# openSX70-dongle.net
KiCad netlist of a schematic drawn in EAGLE
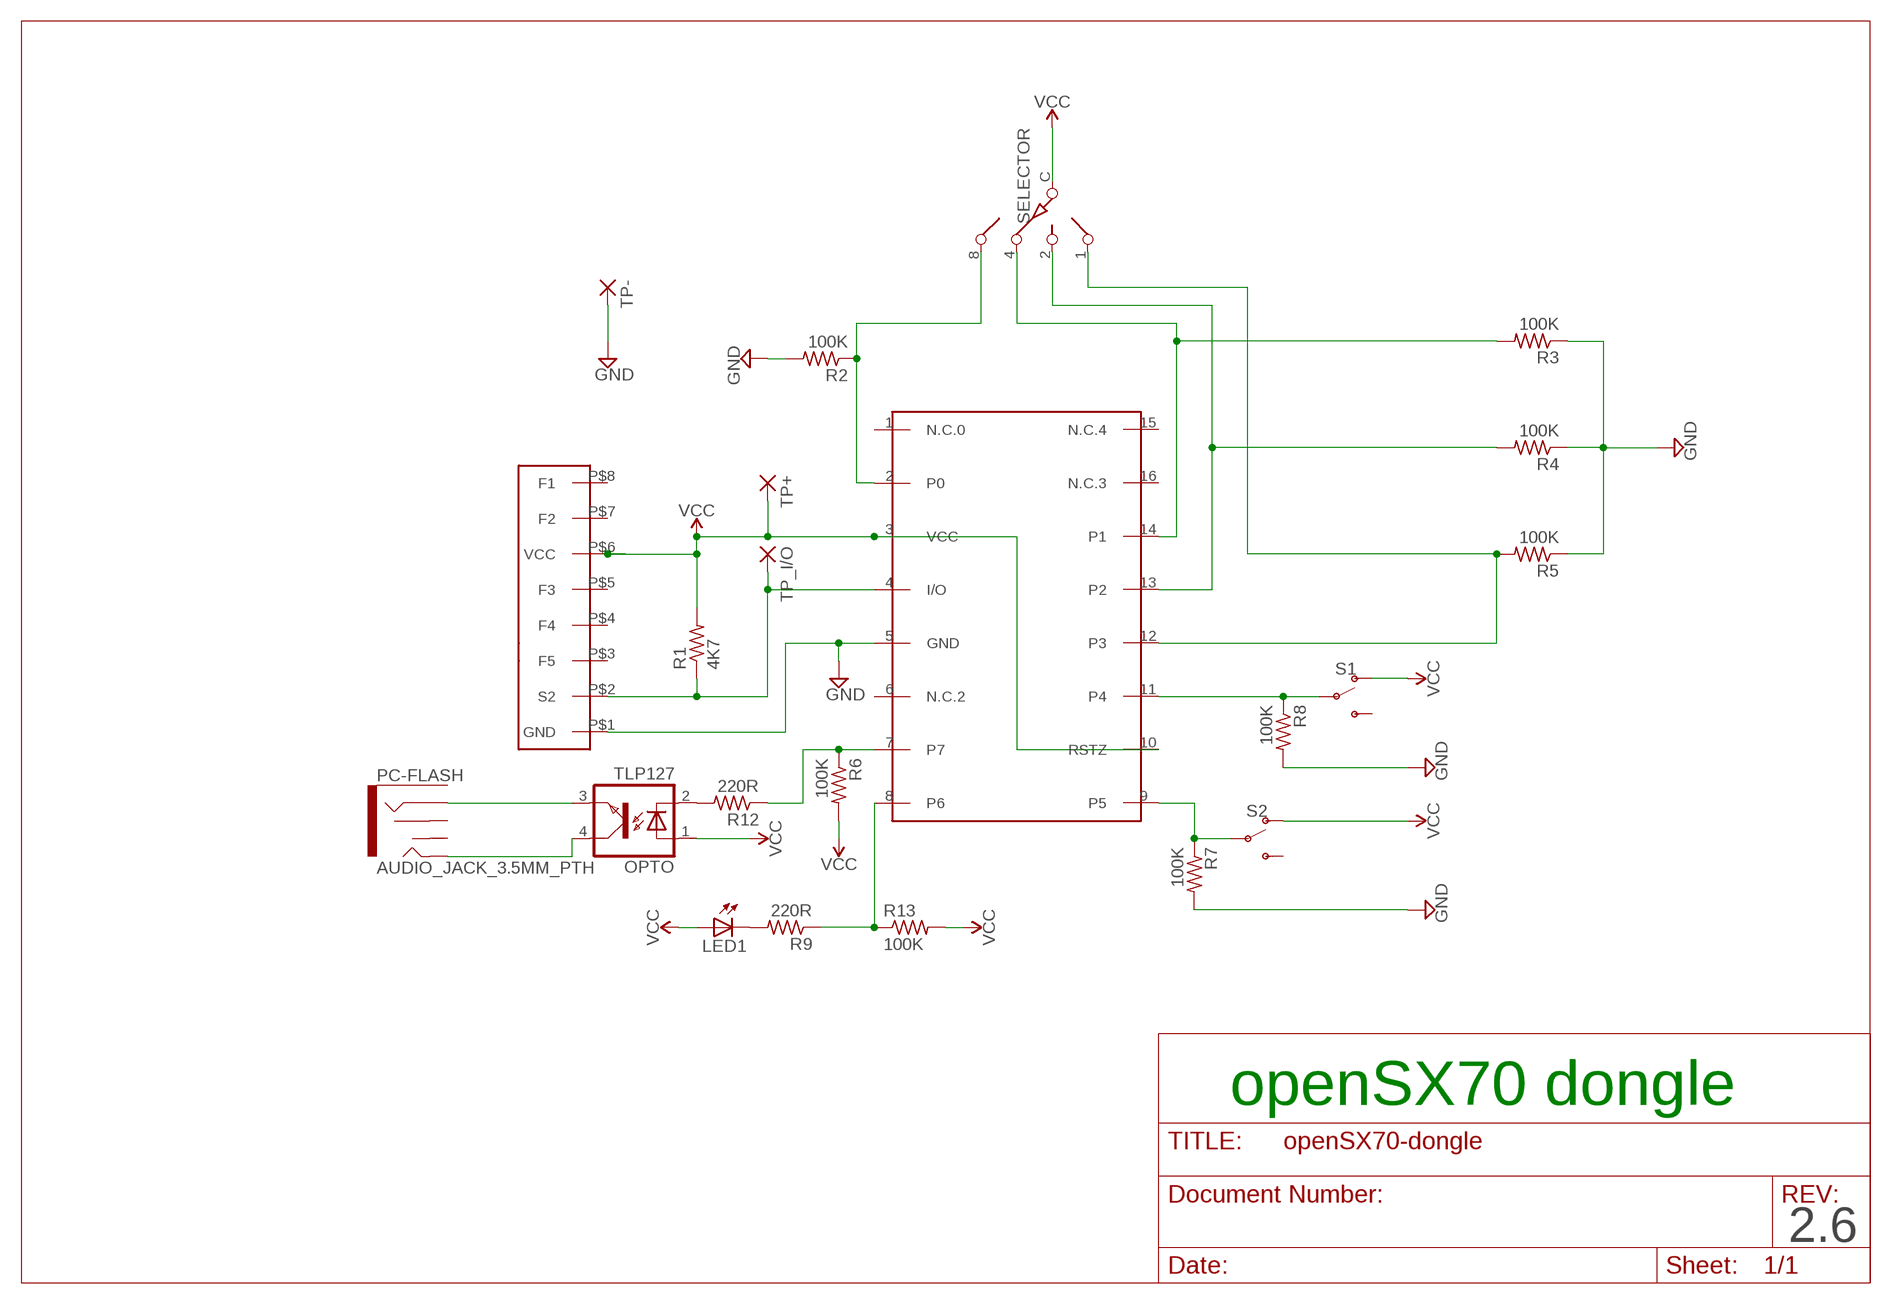
[diagram p0: schematic, sheet 1]

(export (version "E")
  (design (tool "Eeschema 10.0.6"))
  (components
    (comp (ref "DS2408")
      (value "DS2408")
      (footprint "eagle-import:SO16")
      (libsource (lib "eagle-import") (part "DS2408"))
    )
    (comp (ref "LED1")
      (value "LED3MM")
      (footprint "eagle-import:LED3MM")
      (libsource (lib "eagle-import") (part "LED3MM"))
    )
    (comp (ref "OPTO")
      (value "TLP127")
      (footprint "eagle-import:SO-4")
      (libsource (lib "eagle-import") (part "TLP127"))
    )
    (comp (ref "PC-FLASH")
      (value "AUDIO_JACK_3.5MM_PTH")
      (footprint "eagle-import:AUDIO-JACK")
      (libsource (lib "eagle-import") (part "AUDIO_JACK_3.5MM_PTH"))
    )
    (comp (ref "R1")
      (value "4K7")
      (footprint "eagle-import:M0805")
      (libsource (lib "eagle-import") (part "R-US_M0805"))
    )
    (comp (ref "R2")
      (value "100K")
      (footprint "eagle-import:M0805")
      (libsource (lib "eagle-import") (part "R-US_M0805"))
    )
    (comp (ref "R3")
      (value "100K")
      (footprint "eagle-import:M0805")
      (libsource (lib "eagle-import") (part "R-US_M0805"))
    )
    (comp (ref "R4")
      (value "100K")
      (footprint "eagle-import:M0805")
      (libsource (lib "eagle-import") (part "R-US_M0805"))
    )
    (comp (ref "R5")
      (value "100K")
      (footprint "eagle-import:M0805")
      (libsource (lib "eagle-import") (part "R-US_M0805"))
    )
    (comp (ref "R6")
      (value "100K")
      (footprint "eagle-import:M0805")
      (libsource (lib "eagle-import") (part "R-US_M0805"))
    )
    (comp (ref "R7")
      (value "100K")
      (footprint "eagle-import:M0805")
      (libsource (lib "eagle-import") (part "R-US_M0805"))
    )
    (comp (ref "R8")
      (value "100K")
      (footprint "eagle-import:M0805")
      (libsource (lib "eagle-import") (part "R-US_M0805"))
    )
    (comp (ref "R9")
      (value "220R")
      (footprint "eagle-import:M0805")
      (libsource (lib "eagle-import") (part "R-US_M0805"))
    )
    (comp (ref "R12")
      (value "220R")
      (footprint "eagle-import:M0805")
      (libsource (lib "eagle-import") (part "R-US_M0805"))
    )
    (comp (ref "R13")
      (value "100K")
      (footprint "eagle-import:M0805")
      (libsource (lib "eagle-import") (part "R-US_M0805"))
    )
    (comp (ref "S1")
      (value "SWITCH-SPDT-SMD-RIGHT-ANGLE")
      (footprint "eagle-import:SWITCH_SPST_SMD_A")
      (libsource (lib "eagle-import") (part "SWITCH-SPDT-SMD-RIGHT-ANGLE"))
    )
    (comp (ref "S2")
      (value "SWITCH-SPDT-SMD-RIGHT-ANGLE")
      (footprint "eagle-import:SWITCH_SPST_SMD_A")
      (libsource (lib "eagle-import") (part "SWITCH-SPDT-SMD-RIGHT-ANGLE"))
    )
    (comp (ref "SELECTOR")
      (value "SW-C16")
      (footprint "eagle-import:SW-C16")
      (libsource (lib "eagle-import") (part "SW-C16"))
    )
    (comp (ref "TP+")
      (value "SMD2")
      (footprint "eagle-import:SMD1,27-2,54")
      (libsource (lib "eagle-import") (part "SMD2"))
    )
    (comp (ref "TP-")
      (value "SMD2")
      (footprint "eagle-import:SMD1,27-2,54")
      (libsource (lib "eagle-import") (part "SMD2"))
    )
    (comp (ref "TP_I/O")
      (value "SMD2")
      (footprint "eagle-import:SMD1,27-2,54")
      (libsource (lib "eagle-import") (part "SMD2"))
    )
    (comp (ref "U$1")
      (value "FLASH-EDGE-CONNECTOR")
      (footprint "eagle-import:FLASH-EDGE-8")
      (libsource (lib "eagle-import") (part "FLASH-EDGE-CONNECTOR"))
    )
  )
  (nets
    (net (code "1") (name "GND") (class "Default")
      (node (ref "DS2408") (pin "5") (pinfunction "GND_5") (pintype "bidirectional"))
      (node (ref "R2") (pin "2") (pinfunction "2_2") (pintype "passive"))
      (node (ref "R3") (pin "1") (pinfunction "1_1") (pintype "passive"))
      (node (ref "R4") (pin "1") (pinfunction "1_1") (pintype "passive"))
      (node (ref "R5") (pin "1") (pinfunction "1_1") (pintype "passive"))
      (node (ref "R7") (pin "2") (pinfunction "2_2") (pintype "passive"))
      (node (ref "R8") (pin "2") (pinfunction "2_2") (pintype "passive"))
      (node (ref "TP-") (pin "1") (pinfunction "P_1") (pintype "passive"))
      (node (ref "U$1") (pin "P$1") (pinfunction "GND_P$1") (pintype "bidirectional"))
    )
    (net (code "2") (name "Net-(DS2408-I{slash}O)") (class "Default")
      (node (ref "DS2408") (pin "4") (pinfunction "I/O_4") (pintype "bidirectional"))
      (node (ref "R1") (pin "1") (pinfunction "1_1") (pintype "passive"))
      (node (ref "TP_I/O") (pin "1") (pinfunction "P_1") (pintype "passive"))
      (node (ref "U$1") (pin "P$2") (pinfunction "S2_P$2") (pintype "bidirectional"))
    )
    (net (code "3") (name "Net-(DS2408-P0)") (class "Default")
      (node (ref "DS2408") (pin "2") (pinfunction "P0_2") (pintype "bidirectional"))
      (node (ref "R2") (pin "1") (pinfunction "1_1") (pintype "passive"))
      (node (ref "SELECTOR") (pin "8") (pinfunction "8_8") (pintype "passive"))
    )
    (net (code "4") (name "Net-(DS2408-P1)") (class "Default")
      (node (ref "DS2408") (pin "14") (pinfunction "P1_14") (pintype "bidirectional"))
      (node (ref "R3") (pin "2") (pinfunction "2_2") (pintype "passive"))
      (node (ref "SELECTOR") (pin "4") (pinfunction "4_4") (pintype "passive"))
    )
    (net (code "5") (name "Net-(DS2408-P2)") (class "Default")
      (node (ref "DS2408") (pin "13") (pinfunction "P2_13") (pintype "bidirectional"))
      (node (ref "R4") (pin "2") (pinfunction "2_2") (pintype "passive"))
      (node (ref "SELECTOR") (pin "2") (pinfunction "2_2") (pintype "passive"))
    )
    (net (code "6") (name "Net-(DS2408-P3)") (class "Default")
      (node (ref "DS2408") (pin "12") (pinfunction "P3_12") (pintype "bidirectional"))
      (node (ref "R5") (pin "2") (pinfunction "2_2") (pintype "passive"))
      (node (ref "SELECTOR") (pin "1") (pinfunction "1_1") (pintype "passive"))
    )
    (net (code "7") (name "Net-(DS2408-P4)") (class "Default")
      (node (ref "DS2408") (pin "11") (pinfunction "P4_11") (pintype "bidirectional"))
      (node (ref "R8") (pin "1") (pinfunction "1_1") (pintype "passive"))
      (node (ref "S1") (pin "2") (pinfunction "P_2") (pintype "passive"))
    )
    (net (code "8") (name "Net-(DS2408-P5)") (class "Default")
      (node (ref "DS2408") (pin "9") (pinfunction "P5_9") (pintype "bidirectional"))
      (node (ref "R7") (pin "1") (pinfunction "1_1") (pintype "passive"))
      (node (ref "S2") (pin "2") (pinfunction "P_2") (pintype "passive"))
    )
    (net (code "9") (name "Net-(DS2408-P6)") (class "Default")
      (node (ref "DS2408") (pin "8") (pinfunction "P6_8") (pintype "bidirectional"))
      (node (ref "R13") (pin "1") (pinfunction "1_1") (pintype "passive"))
      (node (ref "R9") (pin "1") (pinfunction "1_1") (pintype "passive"))
    )
    (net (code "10") (name "Net-(DS2408-P7)") (class "Default")
      (node (ref "DS2408") (pin "7") (pinfunction "P7_7") (pintype "bidirectional"))
      (node (ref "R12") (pin "1") (pinfunction "1_1") (pintype "passive"))
      (node (ref "R6") (pin "1") (pinfunction "1_1") (pintype "passive"))
    )
    (net (code "11") (name "Net-(LED1-C)") (class "Default")
      (node (ref "LED1") (pin "K") (pinfunction "C_K") (pintype "passive"))
      (node (ref "R9") (pin "2") (pinfunction "2_2") (pintype "passive"))
    )
    (net (code "12") (name "Net-(OPTO-C)") (class "Default")
      (node (ref "OPTO") (pin "2") (pinfunction "C_2") (pintype "passive"))
      (node (ref "R12") (pin "2") (pinfunction "2_2") (pintype "passive"))
    )
    (net (code "13") (name "Net-(OPTO-COL)") (class "Default")
      (node (ref "OPTO") (pin "4") (pinfunction "COL_4") (pintype "passive"))
      (node (ref "PC-FLASH") (pin "TIP") (pinfunction "TIP_TIP") (pintype "bidirectional"))
    )
    (net (code "14") (name "Net-(OPTO-EMIT)") (class "Default")
      (node (ref "OPTO") (pin "3") (pinfunction "EMIT_3") (pintype "passive"))
      (node (ref "PC-FLASH") (pin "RING") (pinfunction "RING_RING") (pintype "bidirectional"))
    )
    (net (code "15") (name "VCC") (class "Default")
      (node (ref "DS2408") (pin "10") (pinfunction "RSTZ_10") (pintype "bidirectional"))
      (node (ref "DS2408") (pin "3") (pinfunction "VCC_3") (pintype "bidirectional"))
      (node (ref "LED1") (pin "A") (pinfunction "A_A") (pintype "passive"))
      (node (ref "OPTO") (pin "1") (pinfunction "A_1") (pintype "passive"))
      (node (ref "R1") (pin "2") (pinfunction "2_2") (pintype "passive"))
      (node (ref "R13") (pin "2") (pinfunction "2_2") (pintype "passive"))
      (node (ref "R6") (pin "2") (pinfunction "2_2") (pintype "passive"))
      (node (ref "S1") (pin "1") (pinfunction "O_1") (pintype "passive"))
      (node (ref "S2") (pin "1") (pinfunction "O_1") (pintype "passive"))
      (node (ref "SELECTOR") (pin "C") (pinfunction "C_C") (pintype "passive"))
      (node (ref "TP+") (pin "1") (pinfunction "P_1") (pintype "passive"))
      (node (ref "U$1") (pin "P$6") (pinfunction "VCC_P$6") (pintype "bidirectional"))
    )
    (net (code "16") (name "unconnected-(DS2408-N.C.0-Pad1)") (class "Default")
      (node (ref "DS2408") (pin "1") (pinfunction "N.C.0_1") (pintype "bidirectional"))
    )
    (net (code "17") (name "unconnected-(DS2408-N.C.2-Pad6)") (class "Default")
      (node (ref "DS2408") (pin "6") (pinfunction "N.C.2_6") (pintype "bidirectional"))
    )
    (net (code "18") (name "unconnected-(DS2408-N.C.3-Pad16)") (class "Default")
      (node (ref "DS2408") (pin "16") (pinfunction "N.C.3_16") (pintype "bidirectional"))
    )
    (net (code "19") (name "unconnected-(DS2408-N.C.4-Pad15)") (class "Default")
      (node (ref "DS2408") (pin "15") (pinfunction "N.C.4_15") (pintype "bidirectional"))
    )
    (net (code "20") (name "unconnected-(PC-FLASH-PadRSH)") (class "Default")
      (node (ref "PC-FLASH") (pin "RSH") (pinfunction "RSH_RSH") (pintype "bidirectional"))
    )
    (net (code "21") (name "unconnected-(PC-FLASH-PadSLEEVE)") (class "Default")
      (node (ref "PC-FLASH") (pin "SLEEVE") (pinfunction "SLEEVE_SLEEVE") (pintype "bidirectional"))
    )
    (net (code "22") (name "unconnected-(PC-FLASH-PadTSH)") (class "Default")
      (node (ref "PC-FLASH") (pin "TSH") (pinfunction "TSH_TSH") (pintype "bidirectional"))
    )
    (net (code "23") (name "unconnected-(S1-S-Pad3)") (class "Default")
      (node (ref "S1") (pin "3") (pinfunction "S_3") (pintype "passive"))
    )
    (net (code "24") (name "unconnected-(S2-S-Pad3)") (class "Default")
      (node (ref "S2") (pin "3") (pinfunction "S_3") (pintype "passive"))
    )
    (net (code "25") (name "unconnected-(U$1-F1-PadP$8)") (class "Default")
      (node (ref "U$1") (pin "P$8") (pinfunction "F1_P$8") (pintype "bidirectional"))
    )
    (net (code "26") (name "unconnected-(U$1-F2-PadP$7)") (class "Default")
      (node (ref "U$1") (pin "P$7") (pinfunction "F2_P$7") (pintype "bidirectional"))
    )
    (net (code "27") (name "unconnected-(U$1-F3-PadP$5)") (class "Default")
      (node (ref "U$1") (pin "P$5") (pinfunction "F3_P$5") (pintype "bidirectional"))
    )
    (net (code "28") (name "unconnected-(U$1-F4-PadP$4)") (class "Default")
      (node (ref "U$1") (pin "P$4") (pinfunction "F4_P$4") (pintype "bidirectional"))
    )
    (net (code "29") (name "unconnected-(U$1-F5-PadP$3)") (class "Default")
      (node (ref "U$1") (pin "P$3") (pinfunction "F5_P$3") (pintype "bidirectional"))
    )
  )
)
